# Memory.net
KiCad netlist of a schematic drawn in Altium Designer
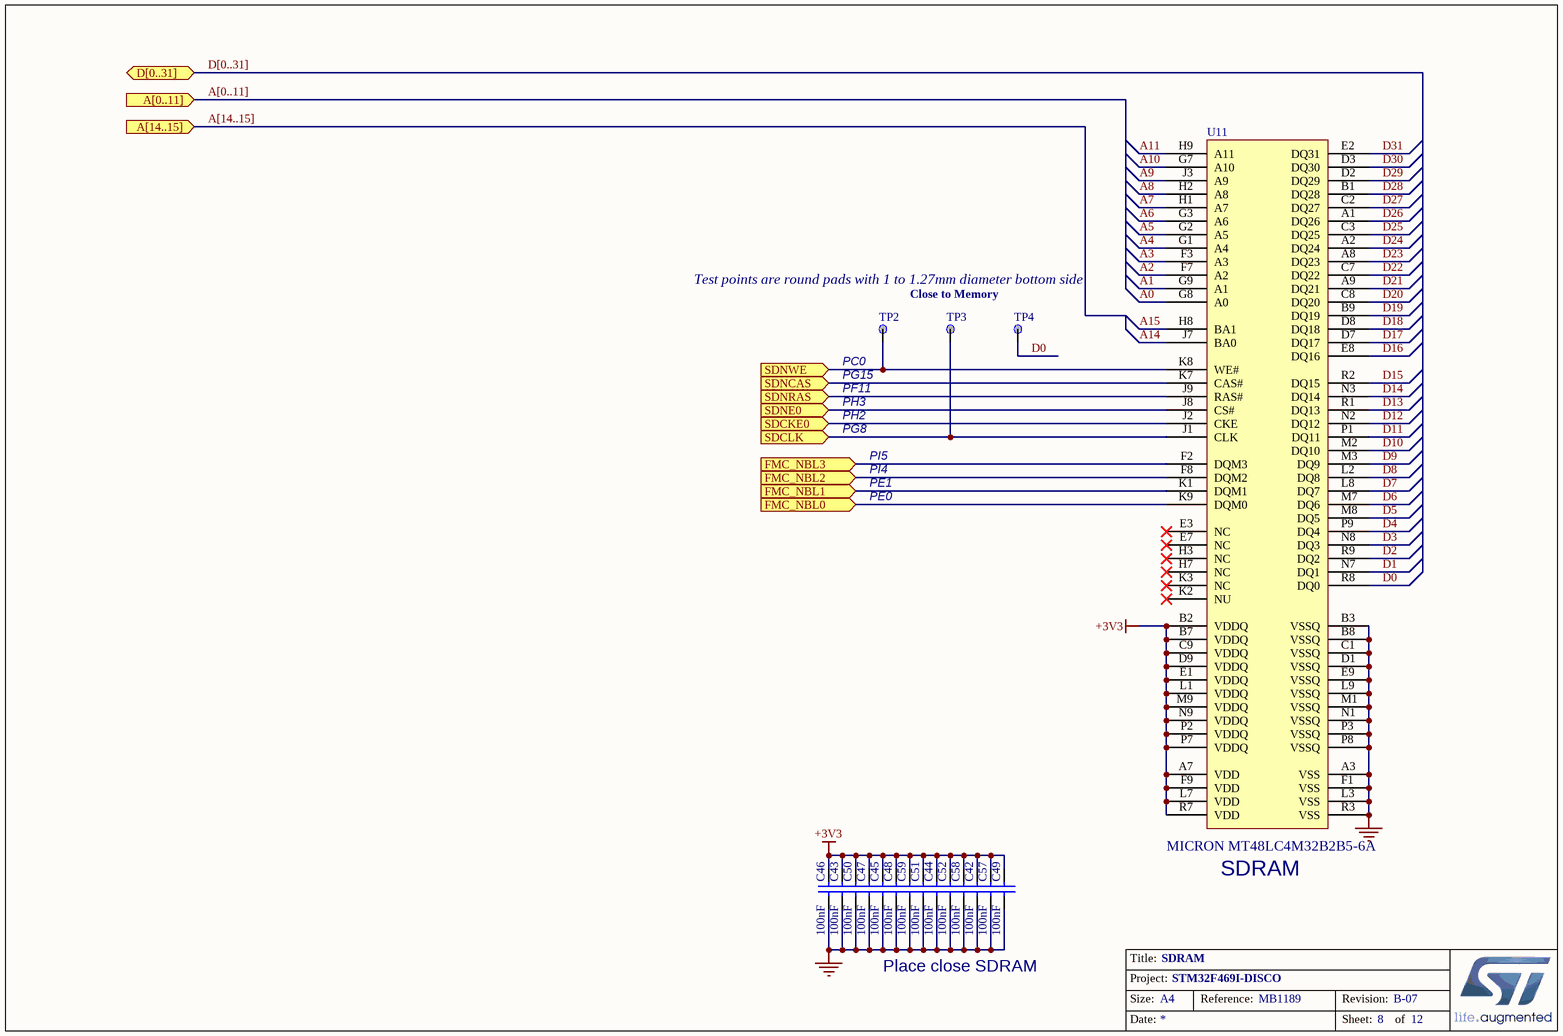
[diagram p0: Memory.SchDoc]

(export (version "E")
  (design (tool "Eeschema 10.0.6"))
  (components
    (comp (ref "C42")
      (value "100nF")
      (footprint "0402C")
      (description "Capacitor")
      (fields (field (name "PUBLISHER") "Altium Limited"))
      (libsource (lib "Miscellaneous Devices") (part "Cap"))
    )
    (comp (ref "C43")
      (value "100nF")
      (footprint "0402C")
      (description "Capacitor")
      (fields (field (name "PUBLISHER") "Altium Limited"))
      (libsource (lib "Miscellaneous Devices") (part "Cap"))
    )
    (comp (ref "C44")
      (value "100nF")
      (footprint "0402C")
      (description "Capacitor")
      (fields (field (name "PUBLISHER") "Altium Limited"))
      (libsource (lib "Miscellaneous Devices") (part "Cap"))
    )
    (comp (ref "C45")
      (value "100nF")
      (footprint "0402C")
      (description "Capacitor")
      (fields (field (name "PUBLISHER") "Altium Limited"))
      (libsource (lib "Miscellaneous Devices") (part "Cap"))
    )
    (comp (ref "C46")
      (value "100nF")
      (footprint "0402C")
      (description "Capacitor")
      (fields (field (name "PUBLISHER") "Altium Limited"))
      (libsource (lib "Miscellaneous Devices") (part "Cap"))
    )
    (comp (ref "C47")
      (value "100nF")
      (footprint "0402C")
      (description "Capacitor")
      (fields (field (name "PUBLISHER") "Altium Limited"))
      (libsource (lib "Miscellaneous Devices") (part "Cap"))
    )
    (comp (ref "C48")
      (value "100nF")
      (footprint "0402C")
      (description "Capacitor")
      (fields (field (name "PUBLISHER") "Altium Limited"))
      (libsource (lib "Miscellaneous Devices") (part "Cap"))
    )
    (comp (ref "C49")
      (value "100nF")
      (footprint "0402C")
      (description "Capacitor")
      (fields (field (name "PUBLISHER") "Altium Limited"))
      (libsource (lib "Miscellaneous Devices") (part "Cap"))
    )
    (comp (ref "C50")
      (value "100nF")
      (footprint "0402C")
      (description "Capacitor")
      (fields (field (name "PUBLISHER") "Altium Limited"))
      (libsource (lib "Miscellaneous Devices") (part "Cap"))
    )
    (comp (ref "C51")
      (value "100nF")
      (footprint "0402C")
      (description "Capacitor")
      (fields (field (name "PUBLISHER") "Altium Limited"))
      (libsource (lib "Miscellaneous Devices") (part "Cap"))
    )
    (comp (ref "C52")
      (value "100nF")
      (footprint "0402C")
      (description "Capacitor")
      (fields (field (name "PUBLISHER") "Altium Limited"))
      (libsource (lib "Miscellaneous Devices") (part "Cap"))
    )
    (comp (ref "C57")
      (value "100nF")
      (footprint "0402C")
      (description "Capacitor")
      (fields (field (name "PUBLISHER") "Altium Limited"))
      (libsource (lib "Miscellaneous Devices") (part "Cap"))
    )
    (comp (ref "C58")
      (value "100nF")
      (footprint "0402C")
      (description "Capacitor")
      (fields (field (name "PUBLISHER") "Altium Limited"))
      (libsource (lib "Miscellaneous Devices") (part "Cap"))
    )
    (comp (ref "C59")
      (value "100nF")
      (footprint "0402C")
      (description "Capacitor")
      (fields (field (name "PUBLISHER") "Altium Limited"))
      (libsource (lib "Miscellaneous Devices") (part "Cap"))
    )
    (comp (ref "TP2") (value "TP") (footprint "TP_C40") (libsource (lib "Almos") (part "TP")))
    (comp (ref "TP3") (value "TP") (footprint "TP_C40") (libsource (lib "Almos") (part "TP")))
    (comp (ref "TP4") (value "TP") (footprint "TP_C40") (libsource (lib "Almos") (part "TP")))
    (comp (ref "U11")
      (value "MICRON MT48LC4M32B2B5-6A")
      (footprint "FBGA90_0R8_8X13")
      (libsource (lib "mb1045") (part "MT48LC4M32B2B5"))
    )
  )
  (nets
    (net (code "1") (name "+3V3") (class "Default")
      (node (ref "C42") (pin "1") (pinfunction "1_1") (pintype "passive"))
      (node (ref "C43") (pin "1") (pinfunction "1_1") (pintype "passive"))
      (node (ref "C44") (pin "1") (pinfunction "1_1") (pintype "passive"))
      (node (ref "C45") (pin "1") (pinfunction "1_1") (pintype "passive"))
      (node (ref "C46") (pin "1") (pinfunction "1_1") (pintype "passive"))
      (node (ref "C47") (pin "1") (pinfunction "1_1") (pintype "passive"))
      (node (ref "C48") (pin "1") (pinfunction "1_1") (pintype "passive"))
      (node (ref "C49") (pin "1") (pinfunction "1_1") (pintype "passive"))
      (node (ref "C50") (pin "1") (pinfunction "1_1") (pintype "passive"))
      (node (ref "C51") (pin "1") (pinfunction "1_1") (pintype "passive"))
      (node (ref "C52") (pin "1") (pinfunction "1_1") (pintype "passive"))
      (node (ref "C57") (pin "1") (pinfunction "1_1") (pintype "passive"))
      (node (ref "C58") (pin "1") (pinfunction "1_1") (pintype "passive"))
      (node (ref "C59") (pin "1") (pinfunction "1_1") (pintype "passive"))
      (node (ref "U11") (pin "A7") (pinfunction "VDD_A7") (pintype "passive"))
      (node (ref "U11") (pin "B2") (pinfunction "VDDQ_B2") (pintype "passive"))
      (node (ref "U11") (pin "B7") (pinfunction "VDDQ_B7") (pintype "passive"))
      (node (ref "U11") (pin "C9") (pinfunction "VDDQ_C9") (pintype "passive"))
      (node (ref "U11") (pin "D9") (pinfunction "VDDQ_D9") (pintype "passive"))
      (node (ref "U11") (pin "E1") (pinfunction "VDDQ_E1") (pintype "passive"))
      (node (ref "U11") (pin "F9") (pinfunction "VDD_F9") (pintype "passive"))
      (node (ref "U11") (pin "L1") (pinfunction "VDDQ_L1") (pintype "passive"))
      (node (ref "U11") (pin "L7") (pinfunction "VDD_L7") (pintype "passive"))
      (node (ref "U11") (pin "M9") (pinfunction "VDDQ_M9") (pintype "passive"))
      (node (ref "U11") (pin "N9") (pinfunction "VDDQ_N9") (pintype "passive"))
      (node (ref "U11") (pin "P2") (pinfunction "VDDQ_P2") (pintype "passive"))
      (node (ref "U11") (pin "P7") (pinfunction "VDDQ_P7") (pintype "passive"))
      (node (ref "U11") (pin "R7") (pinfunction "VDD_R7") (pintype "passive"))
    )
    (net (code "2") (name "/A0") (class "Default")
      (node (ref "U11") (pin "G8") (pinfunction "A0_G8") (pintype "passive"))
    )
    (net (code "3") (name "/A1") (class "Default")
      (node (ref "U11") (pin "G9") (pinfunction "A1_G9") (pintype "passive"))
    )
    (net (code "4") (name "/A2") (class "Default")
      (node (ref "U11") (pin "F7") (pinfunction "A2_F7") (pintype "passive"))
    )
    (net (code "5") (name "/A3") (class "Default")
      (node (ref "U11") (pin "F3") (pinfunction "A3_F3") (pintype "passive"))
    )
    (net (code "6") (name "/A4") (class "Default")
      (node (ref "U11") (pin "G1") (pinfunction "A4_G1") (pintype "passive"))
    )
    (net (code "7") (name "/A5") (class "Default")
      (node (ref "U11") (pin "G2") (pinfunction "A5_G2") (pintype "passive"))
    )
    (net (code "8") (name "/A6") (class "Default")
      (node (ref "U11") (pin "G3") (pinfunction "A6_G3") (pintype "passive"))
    )
    (net (code "9") (name "/A7") (class "Default")
      (node (ref "U11") (pin "H1") (pinfunction "A7_H1") (pintype "passive"))
    )
    (net (code "10") (name "/A8") (class "Default")
      (node (ref "U11") (pin "H2") (pinfunction "A8_H2") (pintype "passive"))
    )
    (net (code "11") (name "/A9") (class "Default")
      (node (ref "U11") (pin "J3") (pinfunction "A9_J3") (pintype "passive"))
    )
    (net (code "12") (name "/A10") (class "Default")
      (node (ref "U11") (pin "G7") (pinfunction "A10_G7") (pintype "passive"))
    )
    (net (code "13") (name "/A11") (class "Default")
      (node (ref "U11") (pin "H9") (pinfunction "A11_H9") (pintype "passive"))
    )
    (net (code "14") (name "/A14") (class "Default")
      (node (ref "U11") (pin "J7") (pinfunction "BA0_J7") (pintype "passive"))
    )
    (net (code "15") (name "/A15") (class "Default")
      (node (ref "U11") (pin "H8") (pinfunction "BA1_H8") (pintype "passive"))
    )
    (net (code "18") (name "/D0") (class "Default")
      (node (ref "TP4") (pin "1") (pinfunction "1_1") (pintype "passive"))
      (node (ref "U11") (pin "R8") (pinfunction "DQ0_R8") (pintype "passive"))
    )
    (net (code "19") (name "/D1") (class "Default")
      (node (ref "U11") (pin "N7") (pinfunction "DQ1_N7") (pintype "passive"))
    )
    (net (code "20") (name "/D2") (class "Default")
      (node (ref "U11") (pin "R9") (pinfunction "DQ2_R9") (pintype "passive"))
    )
    (net (code "21") (name "/D3") (class "Default")
      (node (ref "U11") (pin "N8") (pinfunction "DQ3_N8") (pintype "passive"))
    )
    (net (code "22") (name "/D4") (class "Default")
      (node (ref "U11") (pin "P9") (pinfunction "DQ4_P9") (pintype "passive"))
    )
    (net (code "23") (name "/D5") (class "Default")
      (node (ref "U11") (pin "M8") (pinfunction "DQ5_M8") (pintype "passive"))
    )
    (net (code "24") (name "/D6") (class "Default")
      (node (ref "U11") (pin "M7") (pinfunction "DQ6_M7") (pintype "passive"))
    )
    (net (code "25") (name "/D7") (class "Default")
      (node (ref "U11") (pin "L8") (pinfunction "DQ7_L8") (pintype "passive"))
    )
    (net (code "26") (name "/D8") (class "Default")
      (node (ref "U11") (pin "L2") (pinfunction "DQ8_L2") (pintype "passive"))
    )
    (net (code "27") (name "/D9") (class "Default")
      (node (ref "U11") (pin "M3") (pinfunction "DQ9_M3") (pintype "passive"))
    )
    (net (code "28") (name "/D10") (class "Default")
      (node (ref "U11") (pin "M2") (pinfunction "DQ10_M2") (pintype "passive"))
    )
    (net (code "29") (name "/D11") (class "Default")
      (node (ref "U11") (pin "P1") (pinfunction "DQ11_P1") (pintype "passive"))
    )
    (net (code "30") (name "/D12") (class "Default")
      (node (ref "U11") (pin "N2") (pinfunction "DQ12_N2") (pintype "passive"))
    )
    (net (code "31") (name "/D13") (class "Default")
      (node (ref "U11") (pin "R1") (pinfunction "DQ13_R1") (pintype "passive"))
    )
    (net (code "32") (name "/D14") (class "Default")
      (node (ref "U11") (pin "N3") (pinfunction "DQ14_N3") (pintype "passive"))
    )
    (net (code "33") (name "/D15") (class "Default")
      (node (ref "U11") (pin "R2") (pinfunction "DQ15_R2") (pintype "passive"))
    )
    (net (code "34") (name "/D16") (class "Default")
      (node (ref "U11") (pin "E8") (pinfunction "DQ16_E8") (pintype "passive"))
    )
    (net (code "35") (name "/D17") (class "Default")
      (node (ref "U11") (pin "D7") (pinfunction "DQ17_D7") (pintype "passive"))
    )
    (net (code "36") (name "/D18") (class "Default")
      (node (ref "U11") (pin "D8") (pinfunction "DQ18_D8") (pintype "passive"))
    )
    (net (code "37") (name "/D19") (class "Default")
      (node (ref "U11") (pin "B9") (pinfunction "DQ19_B9") (pintype "passive"))
    )
    (net (code "38") (name "/D20") (class "Default")
      (node (ref "U11") (pin "C8") (pinfunction "DQ20_C8") (pintype "passive"))
    )
    (net (code "39") (name "/D21") (class "Default")
      (node (ref "U11") (pin "A9") (pinfunction "DQ21_A9") (pintype "passive"))
    )
    (net (code "40") (name "/D22") (class "Default")
      (node (ref "U11") (pin "C7") (pinfunction "DQ22_C7") (pintype "passive"))
    )
    (net (code "41") (name "/D23") (class "Default")
      (node (ref "U11") (pin "A8") (pinfunction "DQ23_A8") (pintype "passive"))
    )
    (net (code "42") (name "/D24") (class "Default")
      (node (ref "U11") (pin "A2") (pinfunction "DQ24_A2") (pintype "passive"))
    )
    (net (code "43") (name "/D25") (class "Default")
      (node (ref "U11") (pin "C3") (pinfunction "DQ25_C3") (pintype "passive"))
    )
    (net (code "44") (name "/D26") (class "Default")
      (node (ref "U11") (pin "A1") (pinfunction "DQ26_A1") (pintype "passive"))
    )
    (net (code "45") (name "/D27") (class "Default")
      (node (ref "U11") (pin "C2") (pinfunction "DQ27_C2") (pintype "passive"))
    )
    (net (code "46") (name "/D28") (class "Default")
      (node (ref "U11") (pin "B1") (pinfunction "DQ28_B1") (pintype "passive"))
    )
    (net (code "47") (name "/D29") (class "Default")
      (node (ref "U11") (pin "D2") (pinfunction "DQ29_D2") (pintype "passive"))
    )
    (net (code "48") (name "/D30") (class "Default")
      (node (ref "U11") (pin "D3") (pinfunction "DQ30_D3") (pintype "passive"))
    )
    (net (code "49") (name "/D31") (class "Default")
      (node (ref "U11") (pin "E2") (pinfunction "DQ31_E2") (pintype "passive"))
    )
    (net (code "51") (name "/FMC_NBL0") (class "Default")
      (node (ref "U11") (pin "K9") (pinfunction "DQM0_K9") (pintype "passive"))
    )
    (net (code "52") (name "/FMC_NBL1") (class "Default")
      (node (ref "U11") (pin "K1") (pinfunction "DQM1_K1") (pintype "passive"))
    )
    (net (code "53") (name "/FMC_NBL2") (class "Default")
      (node (ref "U11") (pin "F8") (pinfunction "DQM2_F8") (pintype "passive"))
    )
    (net (code "54") (name "/FMC_NBL3") (class "Default")
      (node (ref "U11") (pin "F2") (pinfunction "DQM3_F2") (pintype "passive"))
    )
    (net (code "55") (name "/SDCKE0") (class "Default")
      (node (ref "U11") (pin "J2") (pinfunction "CKE_J2") (pintype "passive"))
    )
    (net (code "56") (name "/SDCLK") (class "Default")
      (node (ref "TP3") (pin "1") (pinfunction "1_1") (pintype "passive"))
      (node (ref "U11") (pin "J1") (pinfunction "CLK_J1") (pintype "passive"))
    )
    (net (code "57") (name "/SDNCAS") (class "Default")
      (node (ref "U11") (pin "K7") (pinfunction "CAS#_K7") (pintype "passive"))
    )
    (net (code "58") (name "/SDNE0") (class "Default")
      (node (ref "U11") (pin "J8") (pinfunction "CS#_J8") (pintype "passive"))
    )
    (net (code "59") (name "/SDNRAS") (class "Default")
      (node (ref "U11") (pin "J9") (pinfunction "RAS#_J9") (pintype "passive"))
    )
    (net (code "60") (name "/SDNWE") (class "Default")
      (node (ref "TP2") (pin "1") (pinfunction "1_1") (pintype "passive"))
      (node (ref "U11") (pin "K8") (pinfunction "WE#_K8") (pintype "passive"))
    )
    (net (code "61") (name "GND") (class "Default")
      (node (ref "C42") (pin "2") (pinfunction "2_2") (pintype "passive"))
      (node (ref "C43") (pin "2") (pinfunction "2_2") (pintype "passive"))
      (node (ref "C44") (pin "2") (pinfunction "2_2") (pintype "passive"))
      (node (ref "C45") (pin "2") (pinfunction "2_2") (pintype "passive"))
      (node (ref "C46") (pin "2") (pinfunction "2_2") (pintype "passive"))
      (node (ref "C47") (pin "2") (pinfunction "2_2") (pintype "passive"))
      (node (ref "C48") (pin "2") (pinfunction "2_2") (pintype "passive"))
      (node (ref "C49") (pin "2") (pinfunction "2_2") (pintype "passive"))
      (node (ref "C50") (pin "2") (pinfunction "2_2") (pintype "passive"))
      (node (ref "C51") (pin "2") (pinfunction "2_2") (pintype "passive"))
      (node (ref "C52") (pin "2") (pinfunction "2_2") (pintype "passive"))
      (node (ref "C57") (pin "2") (pinfunction "2_2") (pintype "passive"))
      (node (ref "C58") (pin "2") (pinfunction "2_2") (pintype "passive"))
      (node (ref "C59") (pin "2") (pinfunction "2_2") (pintype "passive"))
      (node (ref "U11") (pin "A3") (pinfunction "VSS_A3") (pintype "passive"))
      (node (ref "U11") (pin "B3") (pinfunction "VSSQ_B3") (pintype "passive"))
      (node (ref "U11") (pin "B8") (pinfunction "VSSQ_B8") (pintype "passive"))
      (node (ref "U11") (pin "C1") (pinfunction "VSSQ_C1") (pintype "passive"))
      (node (ref "U11") (pin "D1") (pinfunction "VSSQ_D1") (pintype "passive"))
      (node (ref "U11") (pin "E9") (pinfunction "VSSQ_E9") (pintype "passive"))
      (node (ref "U11") (pin "F1") (pinfunction "VSS_F1") (pintype "passive"))
      (node (ref "U11") (pin "L3") (pinfunction "VSS_L3") (pintype "passive"))
      (node (ref "U11") (pin "L9") (pinfunction "VSSQ_L9") (pintype "passive"))
      (node (ref "U11") (pin "M1") (pinfunction "VSSQ_M1") (pintype "passive"))
      (node (ref "U11") (pin "N1") (pinfunction "VSSQ_N1") (pintype "passive"))
      (node (ref "U11") (pin "P3") (pinfunction "VSSQ_P3") (pintype "passive"))
      (node (ref "U11") (pin "P8") (pinfunction "VSSQ_P8") (pintype "passive"))
      (node (ref "U11") (pin "R3") (pinfunction "VSS_R3") (pintype "passive"))
    )
    (net (code "62") (name "unconnected-(U11-NC-PadE3)") (class "Default")
      (node (ref "U11") (pin "E3") (pinfunction "NC_E3") (pintype "passive+no_connect"))
    )
    (net (code "63") (name "unconnected-(U11-NC-PadE7)") (class "Default")
      (node (ref "U11") (pin "E7") (pinfunction "NC_E7") (pintype "passive+no_connect"))
    )
    (net (code "64") (name "unconnected-(U11-NC-PadH3)") (class "Default")
      (node (ref "U11") (pin "H3") (pinfunction "NC_H3") (pintype "passive+no_connect"))
    )
    (net (code "65") (name "unconnected-(U11-NC-PadH7)") (class "Default")
      (node (ref "U11") (pin "H7") (pinfunction "NC_H7") (pintype "passive+no_connect"))
    )
    (net (code "66") (name "unconnected-(U11-NC-PadK3)") (class "Default")
      (node (ref "U11") (pin "K3") (pinfunction "NC_K3") (pintype "passive+no_connect"))
    )
    (net (code "67") (name "unconnected-(U11-NU-PadK2)") (class "Default")
      (node (ref "U11") (pin "K2") (pinfunction "NU_K2") (pintype "passive+no_connect"))
    )
  )
)
